# FPCs.net
KiCad netlist of a schematic drawn in Altium Designer
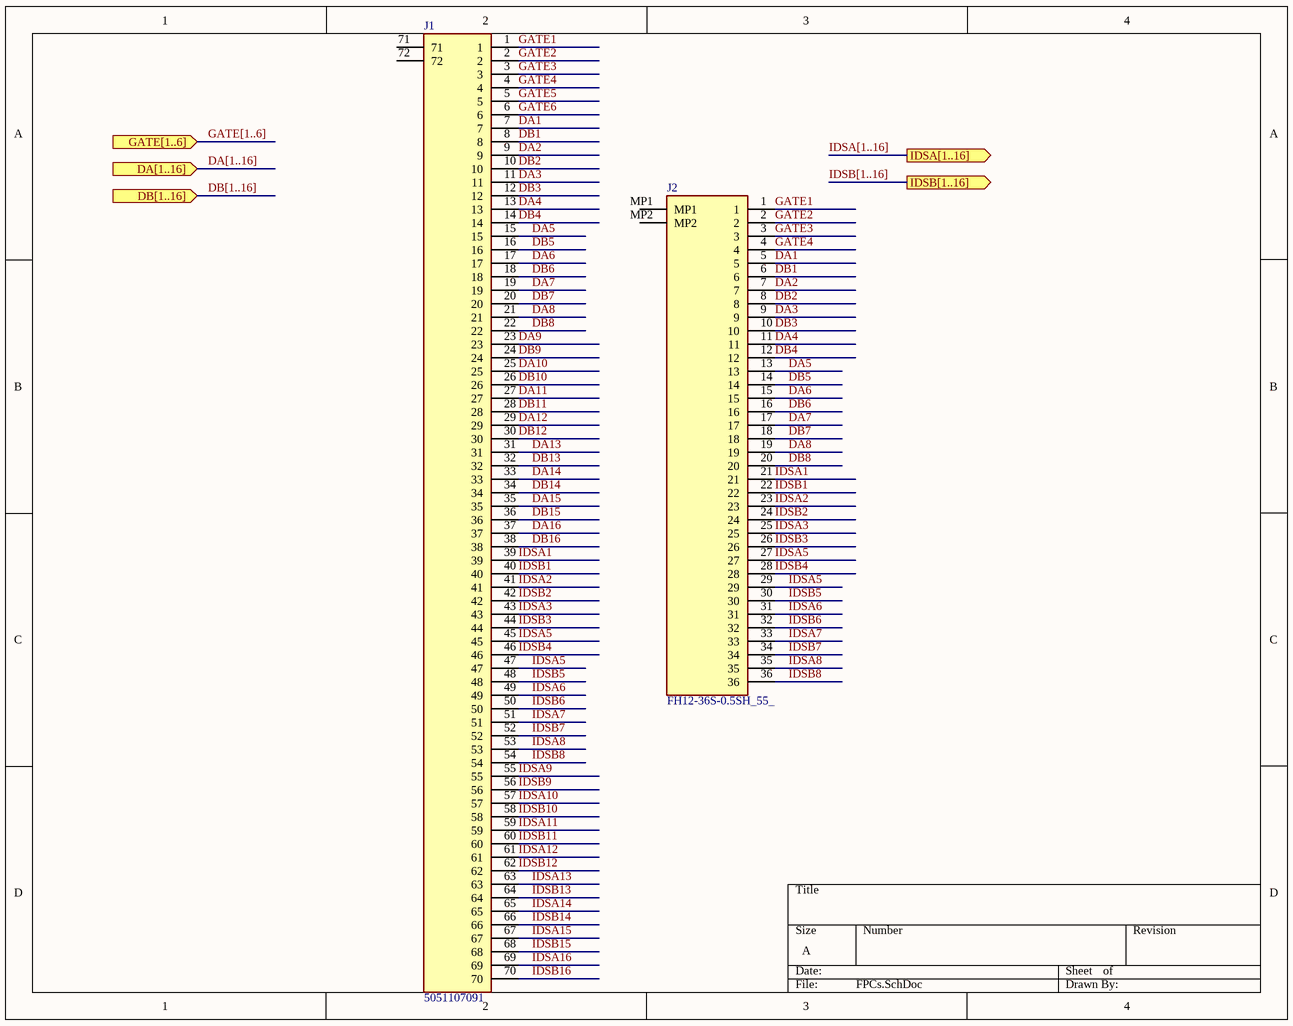
[diagram p0: FPCs.SchDoc]

(export (version "E")
  (design (tool "Eeschema 10.0.6"))
  (components
    (comp (ref "J1")
      (value "5051107091")
      (footprint "SamacSys:5051107091")
      (description "Connector")
      (libsource (lib "SamacSys") (part "5051107091"))
    )
    (comp (ref "J2")
      (value "FH12-36S-0.5SH_55_")
      (footprint "SamacSys:FH1236S05SH55")
      (description "Connector")
      (fields
        (field (name "MANUFACTURER_PART_NUMBER") "FH12-36S-0.5SH(55)")
        (field (name "MOUSER PART NUMBER") "798-FH12-36S-0.5SH55")
      )
      (libsource (lib "SamacSys") (part "FH12-36S-0.5SH_55_"))
    )
  )
  (nets
    (net (code "2") (name "/DA1") (class "Default")
      (node (ref "J1") (pin "7") (pinfunction "7_7") (pintype "passive"))
      (node (ref "J2") (pin "5") (pinfunction "5_5") (pintype "passive"))
    )
    (net (code "3") (name "/DA2") (class "Default")
      (node (ref "J1") (pin "9") (pinfunction "9_9") (pintype "passive"))
      (node (ref "J2") (pin "7") (pinfunction "7_7") (pintype "passive"))
    )
    (net (code "4") (name "/DA3") (class "Default")
      (node (ref "J1") (pin "11") (pinfunction "11_11") (pintype "passive"))
      (node (ref "J2") (pin "9") (pinfunction "9_9") (pintype "passive"))
    )
    (net (code "5") (name "/DA4") (class "Default")
      (node (ref "J1") (pin "13") (pinfunction "13_13") (pintype "passive"))
      (node (ref "J2") (pin "11") (pinfunction "11_11") (pintype "passive"))
    )
    (net (code "6") (name "/DA5") (class "Default")
      (node (ref "J1") (pin "15") (pinfunction "15_15") (pintype "passive"))
      (node (ref "J2") (pin "13") (pinfunction "13_13") (pintype "passive"))
    )
    (net (code "7") (name "/DA6") (class "Default")
      (node (ref "J1") (pin "17") (pinfunction "17_17") (pintype "passive"))
      (node (ref "J2") (pin "15") (pinfunction "15_15") (pintype "passive"))
    )
    (net (code "8") (name "/DA7") (class "Default")
      (node (ref "J1") (pin "19") (pinfunction "19_19") (pintype "passive"))
      (node (ref "J2") (pin "17") (pinfunction "17_17") (pintype "passive"))
    )
    (net (code "9") (name "/DA8") (class "Default")
      (node (ref "J1") (pin "21") (pinfunction "21_21") (pintype "passive"))
      (node (ref "J2") (pin "19") (pinfunction "19_19") (pintype "passive"))
    )
    (net (code "10") (name "/DA9") (class "Default")
      (node (ref "J1") (pin "23") (pinfunction "23_23") (pintype "passive"))
    )
    (net (code "11") (name "/DA10") (class "Default")
      (node (ref "J1") (pin "25") (pinfunction "25_25") (pintype "passive"))
    )
    (net (code "12") (name "/DA11") (class "Default")
      (node (ref "J1") (pin "27") (pinfunction "27_27") (pintype "passive"))
    )
    (net (code "13") (name "/DA12") (class "Default")
      (node (ref "J1") (pin "29") (pinfunction "29_29") (pintype "passive"))
    )
    (net (code "14") (name "/DA13") (class "Default")
      (node (ref "J1") (pin "31") (pinfunction "31_31") (pintype "passive"))
    )
    (net (code "15") (name "/DA14") (class "Default")
      (node (ref "J1") (pin "33") (pinfunction "33_33") (pintype "passive"))
    )
    (net (code "16") (name "/DA15") (class "Default")
      (node (ref "J1") (pin "35") (pinfunction "35_35") (pintype "passive"))
    )
    (net (code "17") (name "/DA16") (class "Default")
      (node (ref "J1") (pin "37") (pinfunction "37_37") (pintype "passive"))
    )
    (net (code "19") (name "/DB1") (class "Default")
      (node (ref "J1") (pin "8") (pinfunction "8_8") (pintype "passive"))
      (node (ref "J2") (pin "6") (pinfunction "6_6") (pintype "passive"))
    )
    (net (code "20") (name "/DB2") (class "Default")
      (node (ref "J1") (pin "10") (pinfunction "10_10") (pintype "passive"))
      (node (ref "J2") (pin "8") (pinfunction "8_8") (pintype "passive"))
    )
    (net (code "21") (name "/DB3") (class "Default")
      (node (ref "J1") (pin "12") (pinfunction "12_12") (pintype "passive"))
      (node (ref "J2") (pin "10") (pinfunction "10_10") (pintype "passive"))
    )
    (net (code "22") (name "/DB4") (class "Default")
      (node (ref "J1") (pin "14") (pinfunction "14_14") (pintype "passive"))
      (node (ref "J2") (pin "12") (pinfunction "12_12") (pintype "passive"))
    )
    (net (code "23") (name "/DB5") (class "Default")
      (node (ref "J1") (pin "16") (pinfunction "16_16") (pintype "passive"))
      (node (ref "J2") (pin "14") (pinfunction "14_14") (pintype "passive"))
    )
    (net (code "24") (name "/DB6") (class "Default")
      (node (ref "J1") (pin "18") (pinfunction "18_18") (pintype "passive"))
      (node (ref "J2") (pin "16") (pinfunction "16_16") (pintype "passive"))
    )
    (net (code "25") (name "/DB7") (class "Default")
      (node (ref "J1") (pin "20") (pinfunction "20_20") (pintype "passive"))
      (node (ref "J2") (pin "18") (pinfunction "18_18") (pintype "passive"))
    )
    (net (code "26") (name "/DB8") (class "Default")
      (node (ref "J1") (pin "22") (pinfunction "22_22") (pintype "passive"))
      (node (ref "J2") (pin "20") (pinfunction "20_20") (pintype "passive"))
    )
    (net (code "27") (name "/DB9") (class "Default")
      (node (ref "J1") (pin "24") (pinfunction "24_24") (pintype "passive"))
    )
    (net (code "28") (name "/DB10") (class "Default")
      (node (ref "J1") (pin "26") (pinfunction "26_26") (pintype "passive"))
    )
    (net (code "29") (name "/DB11") (class "Default")
      (node (ref "J1") (pin "28") (pinfunction "28_28") (pintype "passive"))
    )
    (net (code "30") (name "/DB12") (class "Default")
      (node (ref "J1") (pin "30") (pinfunction "30_30") (pintype "passive"))
    )
    (net (code "31") (name "/DB13") (class "Default")
      (node (ref "J1") (pin "32") (pinfunction "32_32") (pintype "passive"))
    )
    (net (code "32") (name "/DB14") (class "Default")
      (node (ref "J1") (pin "34") (pinfunction "34_34") (pintype "passive"))
    )
    (net (code "33") (name "/DB15") (class "Default")
      (node (ref "J1") (pin "36") (pinfunction "36_36") (pintype "passive"))
    )
    (net (code "34") (name "/DB16") (class "Default")
      (node (ref "J1") (pin "38") (pinfunction "38_38") (pintype "passive"))
    )
    (net (code "36") (name "/GATE1") (class "Default")
      (node (ref "J1") (pin "1") (pinfunction "1_1") (pintype "passive"))
      (node (ref "J2") (pin "1") (pinfunction "1_1") (pintype "passive"))
    )
    (net (code "37") (name "/GATE2") (class "Default")
      (node (ref "J1") (pin "2") (pinfunction "2_2") (pintype "passive"))
      (node (ref "J2") (pin "2") (pinfunction "2_2") (pintype "passive"))
    )
    (net (code "38") (name "/GATE3") (class "Default")
      (node (ref "J1") (pin "3") (pinfunction "3_3") (pintype "passive"))
      (node (ref "J2") (pin "3") (pinfunction "3_3") (pintype "passive"))
    )
    (net (code "39") (name "/GATE4") (class "Default")
      (node (ref "J1") (pin "4") (pinfunction "4_4") (pintype "passive"))
      (node (ref "J2") (pin "4") (pinfunction "4_4") (pintype "passive"))
    )
    (net (code "40") (name "/GATE5") (class "Default")
      (node (ref "J1") (pin "5") (pinfunction "5_5") (pintype "passive"))
    )
    (net (code "41") (name "/GATE6") (class "Default")
      (node (ref "J1") (pin "6") (pinfunction "6_6") (pintype "passive"))
    )
    (net (code "43") (name "/IDSA1") (class "Default")
      (node (ref "J1") (pin "39") (pinfunction "39_39") (pintype "passive"))
      (node (ref "J2") (pin "21") (pinfunction "21_21") (pintype "passive"))
    )
    (net (code "44") (name "/IDSA2") (class "Default")
      (node (ref "J1") (pin "41") (pinfunction "41_41") (pintype "passive"))
      (node (ref "J2") (pin "23") (pinfunction "23_23") (pintype "passive"))
    )
    (net (code "45") (name "/IDSA3") (class "Default")
      (node (ref "J1") (pin "43") (pinfunction "43_43") (pintype "passive"))
      (node (ref "J2") (pin "25") (pinfunction "25_25") (pintype "passive"))
    )
    (net (code "46") (name "/IDSA5") (class "Default")
      (node (ref "J1") (pin "45") (pinfunction "45_45") (pintype "passive"))
      (node (ref "J1") (pin "47") (pinfunction "47_47") (pintype "passive"))
      (node (ref "J2") (pin "27") (pinfunction "27_27") (pintype "passive"))
      (node (ref "J2") (pin "29") (pinfunction "29_29") (pintype "passive"))
    )
    (net (code "47") (name "/IDSA6") (class "Default")
      (node (ref "J1") (pin "49") (pinfunction "49_49") (pintype "passive"))
      (node (ref "J2") (pin "31") (pinfunction "31_31") (pintype "passive"))
    )
    (net (code "48") (name "/IDSA7") (class "Default")
      (node (ref "J1") (pin "51") (pinfunction "51_51") (pintype "passive"))
      (node (ref "J2") (pin "33") (pinfunction "33_33") (pintype "passive"))
    )
    (net (code "49") (name "/IDSA8") (class "Default")
      (node (ref "J1") (pin "53") (pinfunction "53_53") (pintype "passive"))
      (node (ref "J2") (pin "35") (pinfunction "35_35") (pintype "passive"))
    )
    (net (code "50") (name "/IDSA9") (class "Default")
      (node (ref "J1") (pin "55") (pinfunction "55_55") (pintype "passive"))
    )
    (net (code "51") (name "/IDSA10") (class "Default")
      (node (ref "J1") (pin "57") (pinfunction "57_57") (pintype "passive"))
    )
    (net (code "52") (name "/IDSA11") (class "Default")
      (node (ref "J1") (pin "59") (pinfunction "59_59") (pintype "passive"))
    )
    (net (code "53") (name "/IDSA12") (class "Default")
      (node (ref "J1") (pin "61") (pinfunction "61_61") (pintype "passive"))
    )
    (net (code "54") (name "/IDSA13") (class "Default")
      (node (ref "J1") (pin "63") (pinfunction "63_63") (pintype "passive"))
    )
    (net (code "55") (name "/IDSA14") (class "Default")
      (node (ref "J1") (pin "65") (pinfunction "65_65") (pintype "passive"))
    )
    (net (code "56") (name "/IDSA15") (class "Default")
      (node (ref "J1") (pin "67") (pinfunction "67_67") (pintype "passive"))
    )
    (net (code "57") (name "/IDSA16") (class "Default")
      (node (ref "J1") (pin "69") (pinfunction "69_69") (pintype "passive"))
    )
    (net (code "59") (name "/IDSB1") (class "Default")
      (node (ref "J1") (pin "40") (pinfunction "40_40") (pintype "passive"))
      (node (ref "J2") (pin "22") (pinfunction "22_22") (pintype "passive"))
    )
    (net (code "60") (name "/IDSB2") (class "Default")
      (node (ref "J1") (pin "42") (pinfunction "42_42") (pintype "passive"))
      (node (ref "J2") (pin "24") (pinfunction "24_24") (pintype "passive"))
    )
    (net (code "61") (name "/IDSB3") (class "Default")
      (node (ref "J1") (pin "44") (pinfunction "44_44") (pintype "passive"))
      (node (ref "J2") (pin "26") (pinfunction "26_26") (pintype "passive"))
    )
    (net (code "62") (name "/IDSB4") (class "Default")
      (node (ref "J1") (pin "46") (pinfunction "46_46") (pintype "passive"))
      (node (ref "J2") (pin "28") (pinfunction "28_28") (pintype "passive"))
    )
    (net (code "63") (name "/IDSB5") (class "Default")
      (node (ref "J1") (pin "48") (pinfunction "48_48") (pintype "passive"))
      (node (ref "J2") (pin "30") (pinfunction "30_30") (pintype "passive"))
    )
    (net (code "64") (name "/IDSB6") (class "Default")
      (node (ref "J1") (pin "50") (pinfunction "50_50") (pintype "passive"))
      (node (ref "J2") (pin "32") (pinfunction "32_32") (pintype "passive"))
    )
    (net (code "65") (name "/IDSB7") (class "Default")
      (node (ref "J1") (pin "52") (pinfunction "52_52") (pintype "passive"))
      (node (ref "J2") (pin "34") (pinfunction "34_34") (pintype "passive"))
    )
    (net (code "66") (name "/IDSB8") (class "Default")
      (node (ref "J1") (pin "54") (pinfunction "54_54") (pintype "passive"))
      (node (ref "J2") (pin "36") (pinfunction "36_36") (pintype "passive"))
    )
    (net (code "67") (name "/IDSB9") (class "Default")
      (node (ref "J1") (pin "56") (pinfunction "56_56") (pintype "passive"))
    )
    (net (code "68") (name "/IDSB10") (class "Default")
      (node (ref "J1") (pin "58") (pinfunction "58_58") (pintype "passive"))
    )
    (net (code "69") (name "/IDSB11") (class "Default")
      (node (ref "J1") (pin "60") (pinfunction "60_60") (pintype "passive"))
    )
    (net (code "70") (name "/IDSB12") (class "Default")
      (node (ref "J1") (pin "62") (pinfunction "62_62") (pintype "passive"))
    )
    (net (code "71") (name "/IDSB13") (class "Default")
      (node (ref "J1") (pin "64") (pinfunction "64_64") (pintype "passive"))
    )
    (net (code "72") (name "/IDSB14") (class "Default")
      (node (ref "J1") (pin "66") (pinfunction "66_66") (pintype "passive"))
    )
    (net (code "73") (name "/IDSB15") (class "Default")
      (node (ref "J1") (pin "68") (pinfunction "68_68") (pintype "passive"))
    )
    (net (code "74") (name "/IDSB16") (class "Default")
      (node (ref "J1") (pin "70") (pinfunction "70_70") (pintype "passive"))
    )
    (net (code "76") (name "unconnected-(J1-Pad71)") (class "Default")
      (node (ref "J1") (pin "71") (pinfunction "71_71") (pintype "passive"))
    )
    (net (code "77") (name "unconnected-(J1-Pad72)") (class "Default")
      (node (ref "J1") (pin "72") (pinfunction "72_72") (pintype "passive"))
    )
    (net (code "78") (name "unconnected-(J2-PadMP1)") (class "Default")
      (node (ref "J2") (pin "MP1") (pinfunction "MP1_MP1") (pintype "passive"))
    )
    (net (code "79") (name "unconnected-(J2-PadMP2)") (class "Default")
      (node (ref "J2") (pin "MP2") (pinfunction "MP2_MP2") (pintype "passive"))
    )
  )
)
